# 06_-_AUDIO.net
KiCad netlist of a schematic drawn in Altium Designer
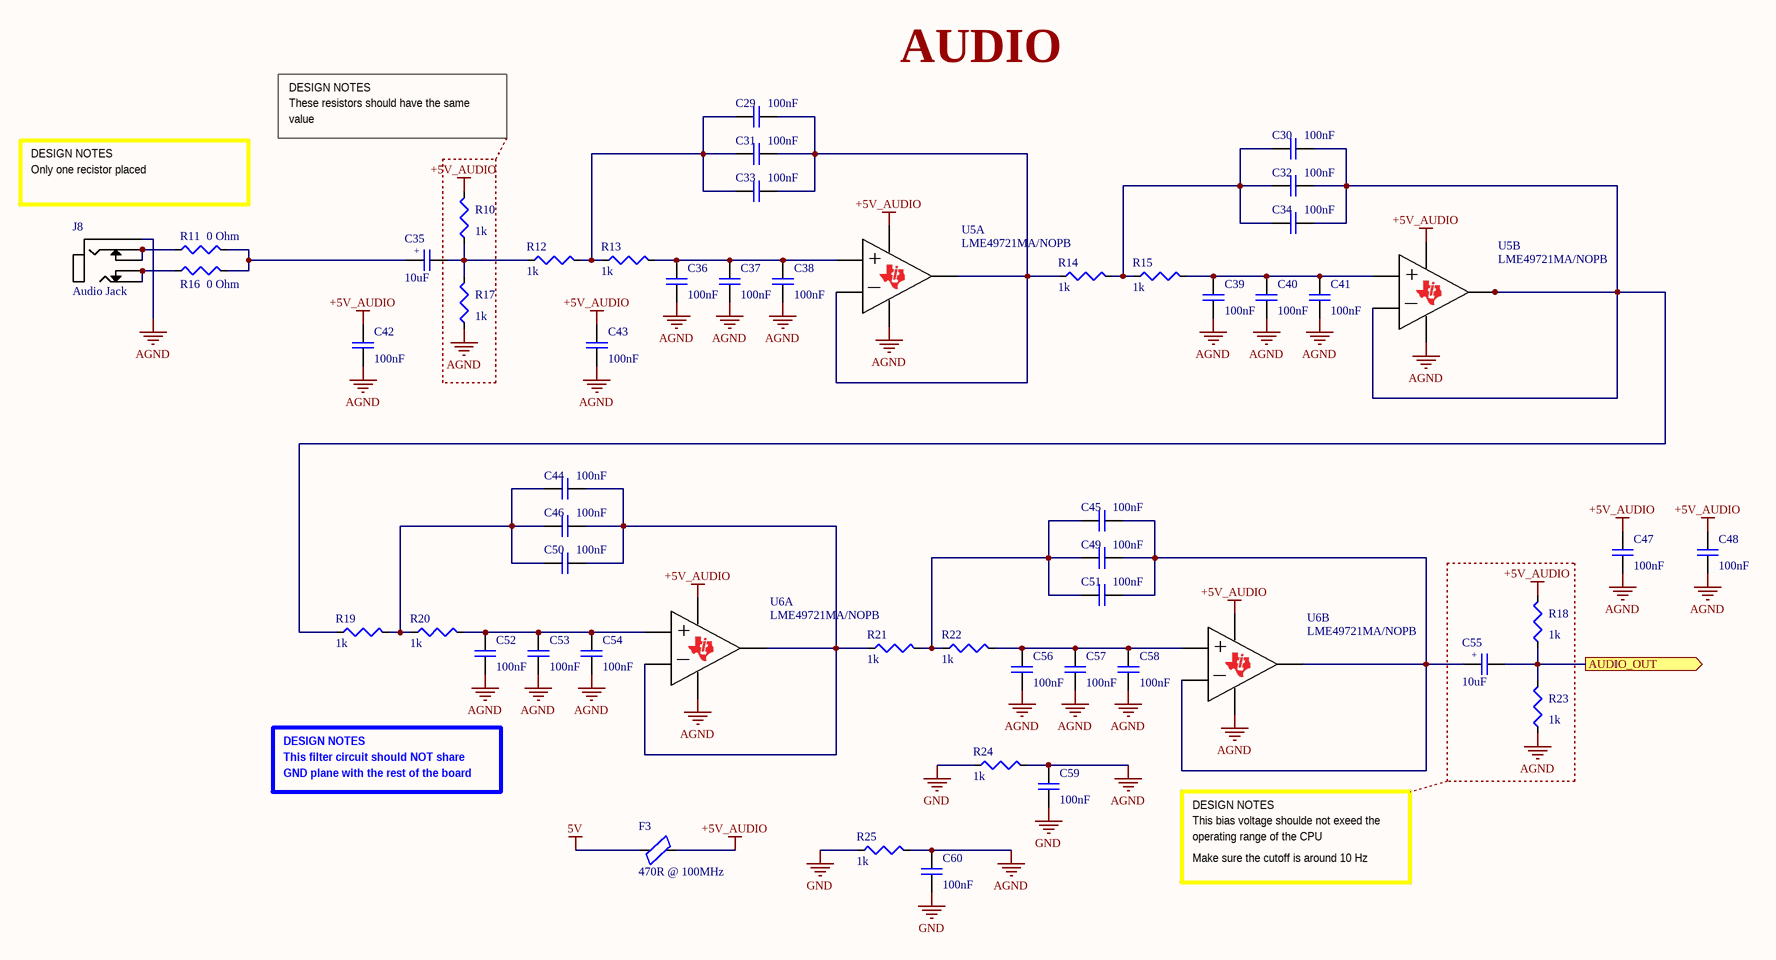
[diagram p0: [06] - AUDIO.SchDoc]

(export (version "E")
  (design (tool "Eeschema 10.0.6"))
  (components
    (comp (ref "C29")
      (value "100nF")
      (footprint "C0603")
      (description "C0603")
      (fields (field (name "Comment") "02016D104KAT2A"))
      (libsource (lib "Passive components") (part "02016D104KAT2A"))
    )
    (comp (ref "C30")
      (value "100nF")
      (footprint "C0603")
      (description "C0603")
      (fields (field (name "Comment") "02016D104KAT2A"))
      (libsource (lib "Passive components") (part "02016D104KAT2A"))
    )
    (comp (ref "C31")
      (value "100nF")
      (footprint "C0603")
      (description "C0603")
      (fields (field (name "Comment") "02016D104KAT2A"))
      (libsource (lib "Passive components") (part "02016D104KAT2A"))
    )
    (comp (ref "C32")
      (value "100nF")
      (footprint "C0603")
      (description "C0603")
      (fields (field (name "Comment") "02016D104KAT2A"))
      (libsource (lib "Passive components") (part "02016D104KAT2A"))
    )
    (comp (ref "C33")
      (value "100nF")
      (footprint "C0603")
      (description "C0603")
      (fields (field (name "Comment") "02016D104KAT2A"))
      (libsource (lib "Passive components") (part "02016D104KAT2A"))
    )
    (comp (ref "C34")
      (value "100nF")
      (footprint "C0603")
      (description "C0603")
      (fields (field (name "Comment") "02016D104KAT2A"))
      (libsource (lib "Passive components") (part "02016D104KAT2A"))
    )
    (comp (ref "C35")
      (value "10uF")
      (footprint "Capacitor electrolytic SMD 4x5.4")
      (description "El. Capacitor SMD 4x5.4")
      (fields (field (name "Comment") "EEE1HA2R2SR"))
      (libsource (lib "Passive components") (part "EEE1HA2R2SR"))
    )
    (comp (ref "C36")
      (value "100nF")
      (footprint "C0603")
      (description "C0603")
      (fields (field (name "Comment") "02016D104KAT2A"))
      (libsource (lib "Passive components") (part "02016D104KAT2A"))
    )
    (comp (ref "C37")
      (value "100nF")
      (footprint "C0603")
      (description "C0603")
      (fields (field (name "Comment") "02016D104KAT2A"))
      (libsource (lib "Passive components") (part "02016D104KAT2A"))
    )
    (comp (ref "C38")
      (value "100nF")
      (footprint "C0603")
      (description "C0603")
      (fields (field (name "Comment") "02016D104KAT2A"))
      (libsource (lib "Passive components") (part "02016D104KAT2A"))
    )
    (comp (ref "C39")
      (value "100nF")
      (footprint "C0603")
      (description "C0603")
      (fields (field (name "Comment") "02016D104KAT2A"))
      (libsource (lib "Passive components") (part "02016D104KAT2A"))
    )
    (comp (ref "C40")
      (value "100nF")
      (footprint "C0603")
      (description "C0603")
      (fields (field (name "Comment") "02016D104KAT2A"))
      (libsource (lib "Passive components") (part "02016D104KAT2A"))
    )
    (comp (ref "C41")
      (value "100nF")
      (footprint "C0603")
      (description "C0603")
      (fields (field (name "Comment") "02016D104KAT2A"))
      (libsource (lib "Passive components") (part "02016D104KAT2A"))
    )
    (comp (ref "C42")
      (value "100nF")
      (footprint "C0603")
      (description "C0603")
      (fields (field (name "Comment") "02016D104KAT2A"))
      (libsource (lib "Passive components") (part "02016D104KAT2A"))
    )
    (comp (ref "C43")
      (value "100nF")
      (footprint "C0603")
      (description "C0603")
      (fields (field (name "Comment") "02016D104KAT2A"))
      (libsource (lib "Passive components") (part "02016D104KAT2A"))
    )
    (comp (ref "C44")
      (value "100nF")
      (footprint "C0603")
      (description "C0603")
      (fields (field (name "Comment") "02016D104KAT2A"))
      (libsource (lib "Passive components") (part "02016D104KAT2A"))
    )
    (comp (ref "C45")
      (value "100nF")
      (footprint "C0603")
      (description "C0603")
      (fields (field (name "Comment") "02016D104KAT2A"))
      (libsource (lib "Passive components") (part "02016D104KAT2A"))
    )
    (comp (ref "C46")
      (value "100nF")
      (footprint "C0603")
      (description "C0603")
      (fields (field (name "Comment") "02016D104KAT2A"))
      (libsource (lib "Passive components") (part "02016D104KAT2A"))
    )
    (comp (ref "C47")
      (value "100nF")
      (footprint "C0603")
      (description "C0603")
      (fields (field (name "Comment") "02016D104KAT2A"))
      (libsource (lib "Passive components") (part "02016D104KAT2A"))
    )
    (comp (ref "C48")
      (value "100nF")
      (footprint "C0603")
      (description "C0603")
      (fields (field (name "Comment") "02016D104KAT2A"))
      (libsource (lib "Passive components") (part "02016D104KAT2A"))
    )
    (comp (ref "C49")
      (value "100nF")
      (footprint "C0603")
      (description "C0603")
      (fields (field (name "Comment") "02016D104KAT2A"))
      (libsource (lib "Passive components") (part "02016D104KAT2A"))
    )
    (comp (ref "C50")
      (value "100nF")
      (footprint "C0603")
      (description "C0603")
      (fields (field (name "Comment") "02016D104KAT2A"))
      (libsource (lib "Passive components") (part "02016D104KAT2A"))
    )
    (comp (ref "C51")
      (value "100nF")
      (footprint "C0603")
      (description "C0603")
      (fields (field (name "Comment") "02016D104KAT2A"))
      (libsource (lib "Passive components") (part "02016D104KAT2A"))
    )
    (comp (ref "C52")
      (value "100nF")
      (footprint "C0603")
      (description "C0603")
      (fields (field (name "Comment") "02016D104KAT2A"))
      (libsource (lib "Passive components") (part "02016D104KAT2A"))
    )
    (comp (ref "C53")
      (value "100nF")
      (footprint "C0603")
      (description "C0603")
      (fields (field (name "Comment") "02016D104KAT2A"))
      (libsource (lib "Passive components") (part "02016D104KAT2A"))
    )
    (comp (ref "C54")
      (value "100nF")
      (footprint "C0603")
      (description "C0603")
      (fields (field (name "Comment") "02016D104KAT2A"))
      (libsource (lib "Passive components") (part "02016D104KAT2A"))
    )
    (comp (ref "C55")
      (value "10uF")
      (footprint "Capacitor electrolytic SMD 4x5.4")
      (description "El. Capacitor SMD 4x5.4")
      (fields (field (name "Comment") "EEE1HA2R2SR"))
      (libsource (lib "Passive components") (part "EEE1HA2R2SR"))
    )
    (comp (ref "C56")
      (value "100nF")
      (footprint "C0603")
      (description "C0603")
      (fields (field (name "Comment") "02016D104KAT2A"))
      (libsource (lib "Passive components") (part "02016D104KAT2A"))
    )
    (comp (ref "C57")
      (value "100nF")
      (footprint "C0603")
      (description "C0603")
      (fields (field (name "Comment") "02016D104KAT2A"))
      (libsource (lib "Passive components") (part "02016D104KAT2A"))
    )
    (comp (ref "C58")
      (value "100nF")
      (footprint "C0603")
      (description "C0603")
      (fields (field (name "Comment") "02016D104KAT2A"))
      (libsource (lib "Passive components") (part "02016D104KAT2A"))
    )
    (comp (ref "C59")
      (value "100nF")
      (footprint "C0603")
      (description "C0603")
      (fields (field (name "Comment") "02016D104KAT2A"))
      (libsource (lib "Passive components") (part "02016D104KAT2A"))
    )
    (comp (ref "C60")
      (value "100nF")
      (footprint "C0603")
      (description "C0603")
      (fields (field (name "Comment") "02016D104KAT2A"))
      (libsource (lib "Passive components") (part "02016D104KAT2A"))
    )
    (comp (ref "F3")
      (value "470R @ 100MHz")
      (footprint "Ferrite bead 0603")
      (description "Ferrite bead 0603")
      (fields (field (name "Comment") "BLM18AG121SN1D"))
      (libsource (lib "Passive components") (part "BLM18AG121SN1D"))
    )
    (comp (ref "J8")
      (value "Audio Jack")
      (footprint "Audio jack flat")
      (description "Audio jack flat 5 contacts")
      (libsource (lib "Connectors") (part "FC68133"))
    )
    (comp (ref "R10")
      (value "1k")
      (footprint "R0603")
      (description "R0603")
      (fields (field (name "Comment") "CPF-A-0603B100KE1"))
      (libsource (lib "Passive components") (part "CPF-A-0603B100KE1"))
    )
    (comp (ref "R11")
      (value "0 Ohm")
      (footprint "R0603")
      (description "R0603")
      (fields (field (name "Comment") "CPF-A-0603B100KE1"))
      (libsource (lib "Passive components") (part "CPF-A-0603B100KE1"))
    )
    (comp (ref "R12")
      (value "1k")
      (footprint "R0603")
      (description "R0603")
      (fields (field (name "Comment") "CPF-A-0603B100KE1"))
      (libsource (lib "Passive components") (part "CPF-A-0603B100KE1"))
    )
    (comp (ref "R13")
      (value "1k")
      (footprint "R0603")
      (description "R0603")
      (fields (field (name "Comment") "CPF-A-0603B100KE1"))
      (libsource (lib "Passive components") (part "CPF-A-0603B100KE1"))
    )
    (comp (ref "R14")
      (value "1k")
      (footprint "R0603")
      (description "R0603")
      (fields (field (name "Comment") "CPF-A-0603B100KE1"))
      (libsource (lib "Passive components") (part "CPF-A-0603B100KE1"))
    )
    (comp (ref "R15")
      (value "1k")
      (footprint "R0603")
      (description "R0603")
      (fields (field (name "Comment") "CPF-A-0603B100KE1"))
      (libsource (lib "Passive components") (part "CPF-A-0603B100KE1"))
    )
    (comp (ref "R16")
      (value "0 Ohm")
      (footprint "R0603")
      (description "R0603")
      (fields (field (name "Comment") "CPF-A-0603B100KE1"))
      (libsource (lib "Passive components") (part "CPF-A-0603B100KE1"))
    )
    (comp (ref "R17")
      (value "1k")
      (footprint "R0603")
      (description "R0603")
      (fields (field (name "Comment") "CPF-A-0603B100KE1"))
      (libsource (lib "Passive components") (part "CPF-A-0603B100KE1"))
    )
    (comp (ref "R18")
      (value "1k")
      (footprint "R0603")
      (description "R0603")
      (fields (field (name "Comment") "CPF-A-0603B100KE1"))
      (libsource (lib "Passive components") (part "CPF-A-0603B100KE1"))
    )
    (comp (ref "R19")
      (value "1k")
      (footprint "R0603")
      (description "R0603")
      (fields (field (name "Comment") "CPF-A-0603B100KE1"))
      (libsource (lib "Passive components") (part "CPF-A-0603B100KE1"))
    )
    (comp (ref "R20")
      (value "1k")
      (footprint "R0603")
      (description "R0603")
      (fields (field (name "Comment") "CPF-A-0603B100KE1"))
      (libsource (lib "Passive components") (part "CPF-A-0603B100KE1"))
    )
    (comp (ref "R21")
      (value "1k")
      (footprint "R0603")
      (description "R0603")
      (fields (field (name "Comment") "CPF-A-0603B100KE1"))
      (libsource (lib "Passive components") (part "CPF-A-0603B100KE1"))
    )
    (comp (ref "R22")
      (value "1k")
      (footprint "R0603")
      (description "R0603")
      (fields (field (name "Comment") "CPF-A-0603B100KE1"))
      (libsource (lib "Passive components") (part "CPF-A-0603B100KE1"))
    )
    (comp (ref "R23")
      (value "1k")
      (footprint "R0603")
      (description "R0603")
      (fields (field (name "Comment") "CPF-A-0603B100KE1"))
      (libsource (lib "Passive components") (part "CPF-A-0603B100KE1"))
    )
    (comp (ref "R24")
      (value "1k")
      (footprint "R0603")
      (description "R0603")
      (fields (field (name "Comment") "CPF-A-0603B100KE1"))
      (libsource (lib "Passive components") (part "CPF-A-0603B100KE1"))
    )
    (comp (ref "R25")
      (value "1k")
      (footprint "R0603")
      (description "R0603")
      (fields (field (name "Comment") "CPF-A-0603B100KE1"))
      (libsource (lib "Passive components") (part "CPF-A-0603B100KE1"))
    )
    (comp (ref "U5")
      (value "LME49721MA/NOPB")
      (footprint "LME49721MA/NOPB")
      (description "Audio OP amp, single supply, low voltage")
      (libsource (lib "IC") (part "LME49721MA/NOPB"))
    )
    (comp (ref "U6")
      (value "LME49721MA/NOPB")
      (footprint "LME49721MA/NOPB")
      (description "Audio OP amp, single supply, low voltage")
      (libsource (lib "IC") (part "LME49721MA/NOPB"))
    )
  )
  (nets
    (net (code "1") (name "+5V_AUDIO") (class "Default")
      (node (ref "C42") (pin "2") (pinfunction "2_2") (pintype "passive"))
      (node (ref "C43") (pin "2") (pinfunction "2_2") (pintype "passive"))
      (node (ref "C47") (pin "2") (pinfunction "2_2") (pintype "passive"))
      (node (ref "C48") (pin "2") (pinfunction "2_2") (pintype "passive"))
      (node (ref "F3") (pin "2") (pinfunction "2_2") (pintype "passive"))
      (node (ref "R10") (pin "2") (pinfunction "2_2") (pintype "passive"))
      (node (ref "R18") (pin "2") (pinfunction "2_2") (pintype "passive"))
      (node (ref "U5") (pin "8") (pinfunction "VDD_8") (pintype "passive"))
      (node (ref "U6") (pin "8") (pinfunction "VDD_8") (pintype "passive"))
    )
    (net (code "2") (name "/AUDIO_OUT") (class "Default")
      (node (ref "C55") (pin "2") (pinfunction "2_2") (pintype "passive"))
      (node (ref "R18") (pin "1") (pinfunction "1_1") (pintype "passive"))
      (node (ref "R23") (pin "2") (pinfunction "2_2") (pintype "passive"))
    )
    (net (code "3") (name "5V") (class "Default")
      (node (ref "F3") (pin "1") (pinfunction "1_1") (pintype "passive"))
    )
    (net (code "4") (name "AGND") (class "Default")
      (node (ref "C36") (pin "1") (pinfunction "1_1") (pintype "passive"))
      (node (ref "C37") (pin "1") (pinfunction "1_1") (pintype "passive"))
      (node (ref "C38") (pin "1") (pinfunction "1_1") (pintype "passive"))
      (node (ref "C39") (pin "1") (pinfunction "1_1") (pintype "passive"))
      (node (ref "C40") (pin "1") (pinfunction "1_1") (pintype "passive"))
      (node (ref "C41") (pin "1") (pinfunction "1_1") (pintype "passive"))
      (node (ref "C42") (pin "1") (pinfunction "1_1") (pintype "passive"))
      (node (ref "C43") (pin "1") (pinfunction "1_1") (pintype "passive"))
      (node (ref "C47") (pin "1") (pinfunction "1_1") (pintype "passive"))
      (node (ref "C48") (pin "1") (pinfunction "1_1") (pintype "passive"))
      (node (ref "C52") (pin "1") (pinfunction "1_1") (pintype "passive"))
      (node (ref "C53") (pin "1") (pinfunction "1_1") (pintype "passive"))
      (node (ref "C54") (pin "1") (pinfunction "1_1") (pintype "passive"))
      (node (ref "C56") (pin "1") (pinfunction "1_1") (pintype "passive"))
      (node (ref "C57") (pin "1") (pinfunction "1_1") (pintype "passive"))
      (node (ref "C58") (pin "1") (pinfunction "1_1") (pintype "passive"))
      (node (ref "C59") (pin "2") (pinfunction "2_2") (pintype "passive"))
      (node (ref "C60") (pin "2") (pinfunction "2_2") (pintype "passive"))
      (node (ref "J8") (pin "1") (pinfunction "1_1") (pintype "passive"))
      (node (ref "R17") (pin "1") (pinfunction "1_1") (pintype "passive"))
      (node (ref "R23") (pin "1") (pinfunction "1_1") (pintype "passive"))
      (node (ref "R24") (pin "2") (pinfunction "2_2") (pintype "passive"))
      (node (ref "R25") (pin "2") (pinfunction "2_2") (pintype "passive"))
      (node (ref "U5") (pin "4") (pinfunction "VDD_4") (pintype "passive"))
      (node (ref "U6") (pin "4") (pinfunction "VDD_4") (pintype "passive"))
    )
    (net (code "5") (name "GND") (class "Default")
      (node (ref "C59") (pin "1") (pinfunction "1_1") (pintype "passive"))
      (node (ref "C60") (pin "1") (pinfunction "1_1") (pintype "passive"))
      (node (ref "R24") (pin "1") (pinfunction "1_1") (pintype "passive"))
      (node (ref "R25") (pin "1") (pinfunction "1_1") (pintype "passive"))
    )
    (net (code "6") (name "Net-(C29-Pad1)") (class "Default")
      (node (ref "C29") (pin "1") (pinfunction "1_1") (pintype "passive"))
      (node (ref "C31") (pin "1") (pinfunction "1_1") (pintype "passive"))
      (node (ref "C33") (pin "1") (pinfunction "1_1") (pintype "passive"))
      (node (ref "R12") (pin "2") (pinfunction "2_2") (pintype "passive"))
      (node (ref "R13") (pin "1") (pinfunction "1_1") (pintype "passive"))
    )
    (net (code "7") (name "Net-(C29-Pad2)") (class "Default")
      (node (ref "C29") (pin "2") (pinfunction "2_2") (pintype "passive"))
      (node (ref "C31") (pin "2") (pinfunction "2_2") (pintype "passive"))
      (node (ref "C33") (pin "2") (pinfunction "2_2") (pintype "passive"))
      (node (ref "R14") (pin "1") (pinfunction "1_1") (pintype "passive"))
      (node (ref "U5") (pin "1") (pinfunction "VDD_1") (pintype "passive"))
      (node (ref "U5") (pin "2") (pinfunction "VDD_2") (pintype "passive"))
    )
    (net (code "8") (name "Net-(C30-Pad1)") (class "Default")
      (node (ref "C30") (pin "1") (pinfunction "1_1") (pintype "passive"))
      (node (ref "C32") (pin "1") (pinfunction "1_1") (pintype "passive"))
      (node (ref "C34") (pin "1") (pinfunction "1_1") (pintype "passive"))
      (node (ref "R14") (pin "2") (pinfunction "2_2") (pintype "passive"))
      (node (ref "R15") (pin "1") (pinfunction "1_1") (pintype "passive"))
    )
    (net (code "9") (name "Net-(C30-Pad2)") (class "Default")
      (node (ref "C30") (pin "2") (pinfunction "2_2") (pintype "passive"))
      (node (ref "C32") (pin "2") (pinfunction "2_2") (pintype "passive"))
      (node (ref "C34") (pin "2") (pinfunction "2_2") (pintype "passive"))
      (node (ref "R19") (pin "1") (pinfunction "1_1") (pintype "passive"))
      (node (ref "U5") (pin "6") (pinfunction "VDD_6") (pintype "passive"))
      (node (ref "U5") (pin "7") (pinfunction "VDD_7") (pintype "passive"))
    )
    (net (code "10") (name "Net-(C35-Pad1)") (class "Default")
      (node (ref "C35") (pin "1") (pinfunction "1_1") (pintype "passive"))
      (node (ref "R11") (pin "2") (pinfunction "2_2") (pintype "passive"))
      (node (ref "R16") (pin "2") (pinfunction "2_2") (pintype "passive"))
    )
    (net (code "11") (name "Net-(C35-Pad2)") (class "Default")
      (node (ref "C35") (pin "2") (pinfunction "2_2") (pintype "passive"))
      (node (ref "R10") (pin "1") (pinfunction "1_1") (pintype "passive"))
      (node (ref "R12") (pin "1") (pinfunction "1_1") (pintype "passive"))
      (node (ref "R17") (pin "2") (pinfunction "2_2") (pintype "passive"))
    )
    (net (code "12") (name "Net-(C36-Pad2)") (class "Default")
      (node (ref "C36") (pin "2") (pinfunction "2_2") (pintype "passive"))
      (node (ref "C37") (pin "2") (pinfunction "2_2") (pintype "passive"))
      (node (ref "C38") (pin "2") (pinfunction "2_2") (pintype "passive"))
      (node (ref "R13") (pin "2") (pinfunction "2_2") (pintype "passive"))
      (node (ref "U5") (pin "3") (pinfunction "VDD_3") (pintype "passive"))
    )
    (net (code "13") (name "Net-(C39-Pad2)") (class "Default")
      (node (ref "C39") (pin "2") (pinfunction "2_2") (pintype "passive"))
      (node (ref "C40") (pin "2") (pinfunction "2_2") (pintype "passive"))
      (node (ref "C41") (pin "2") (pinfunction "2_2") (pintype "passive"))
      (node (ref "R15") (pin "2") (pinfunction "2_2") (pintype "passive"))
      (node (ref "U5") (pin "5") (pinfunction "VDD_5") (pintype "passive"))
    )
    (net (code "14") (name "Net-(C44-Pad1)") (class "Default")
      (node (ref "C44") (pin "1") (pinfunction "1_1") (pintype "passive"))
      (node (ref "C46") (pin "1") (pinfunction "1_1") (pintype "passive"))
      (node (ref "C50") (pin "1") (pinfunction "1_1") (pintype "passive"))
      (node (ref "R19") (pin "2") (pinfunction "2_2") (pintype "passive"))
      (node (ref "R20") (pin "1") (pinfunction "1_1") (pintype "passive"))
    )
    (net (code "15") (name "Net-(C44-Pad2)") (class "Default")
      (node (ref "C44") (pin "2") (pinfunction "2_2") (pintype "passive"))
      (node (ref "C46") (pin "2") (pinfunction "2_2") (pintype "passive"))
      (node (ref "C50") (pin "2") (pinfunction "2_2") (pintype "passive"))
      (node (ref "R21") (pin "1") (pinfunction "1_1") (pintype "passive"))
      (node (ref "U6") (pin "1") (pinfunction "VDD_1") (pintype "passive"))
      (node (ref "U6") (pin "2") (pinfunction "VDD_2") (pintype "passive"))
    )
    (net (code "16") (name "Net-(C45-Pad1)") (class "Default")
      (node (ref "C45") (pin "1") (pinfunction "1_1") (pintype "passive"))
      (node (ref "C49") (pin "1") (pinfunction "1_1") (pintype "passive"))
      (node (ref "C51") (pin "1") (pinfunction "1_1") (pintype "passive"))
      (node (ref "R21") (pin "2") (pinfunction "2_2") (pintype "passive"))
      (node (ref "R22") (pin "1") (pinfunction "1_1") (pintype "passive"))
    )
    (net (code "17") (name "Net-(C45-Pad2)") (class "Default")
      (node (ref "C45") (pin "2") (pinfunction "2_2") (pintype "passive"))
      (node (ref "C49") (pin "2") (pinfunction "2_2") (pintype "passive"))
      (node (ref "C51") (pin "2") (pinfunction "2_2") (pintype "passive"))
      (node (ref "C55") (pin "1") (pinfunction "1_1") (pintype "passive"))
      (node (ref "U6") (pin "6") (pinfunction "VDD_6") (pintype "passive"))
      (node (ref "U6") (pin "7") (pinfunction "VDD_7") (pintype "passive"))
    )
    (net (code "18") (name "Net-(C52-Pad2)") (class "Default")
      (node (ref "C52") (pin "2") (pinfunction "2_2") (pintype "passive"))
      (node (ref "C53") (pin "2") (pinfunction "2_2") (pintype "passive"))
      (node (ref "C54") (pin "2") (pinfunction "2_2") (pintype "passive"))
      (node (ref "R20") (pin "2") (pinfunction "2_2") (pintype "passive"))
      (node (ref "U6") (pin "3") (pinfunction "VDD_3") (pintype "passive"))
    )
    (net (code "19") (name "Net-(C56-Pad2)") (class "Default")
      (node (ref "C56") (pin "2") (pinfunction "2_2") (pintype "passive"))
      (node (ref "C57") (pin "2") (pinfunction "2_2") (pintype "passive"))
      (node (ref "C58") (pin "2") (pinfunction "2_2") (pintype "passive"))
      (node (ref "R22") (pin "2") (pinfunction "2_2") (pintype "passive"))
      (node (ref "U6") (pin "5") (pinfunction "VDD_5") (pintype "passive"))
    )
    (net (code "20") (name "Net-(J8-Pad2)") (class "Default")
      (node (ref "J8") (pin "2") (pinfunction "2_2") (pintype "passive"))
      (node (ref "J8") (pin "3") (pinfunction "3_3") (pintype "passive"))
      (node (ref "R11") (pin "1") (pinfunction "1_1") (pintype "passive"))
    )
    (net (code "21") (name "Net-(J8-Pad4)") (class "Default")
      (node (ref "J8") (pin "4") (pinfunction "4_4") (pintype "passive"))
      (node (ref "J8") (pin "5") (pinfunction "5_5") (pintype "passive"))
      (node (ref "R16") (pin "1") (pinfunction "1_1") (pintype "passive"))
    )
  )
)
